# JlinkV9_RST.net
KiCad netlist of a schematic drawn in Altium Designer
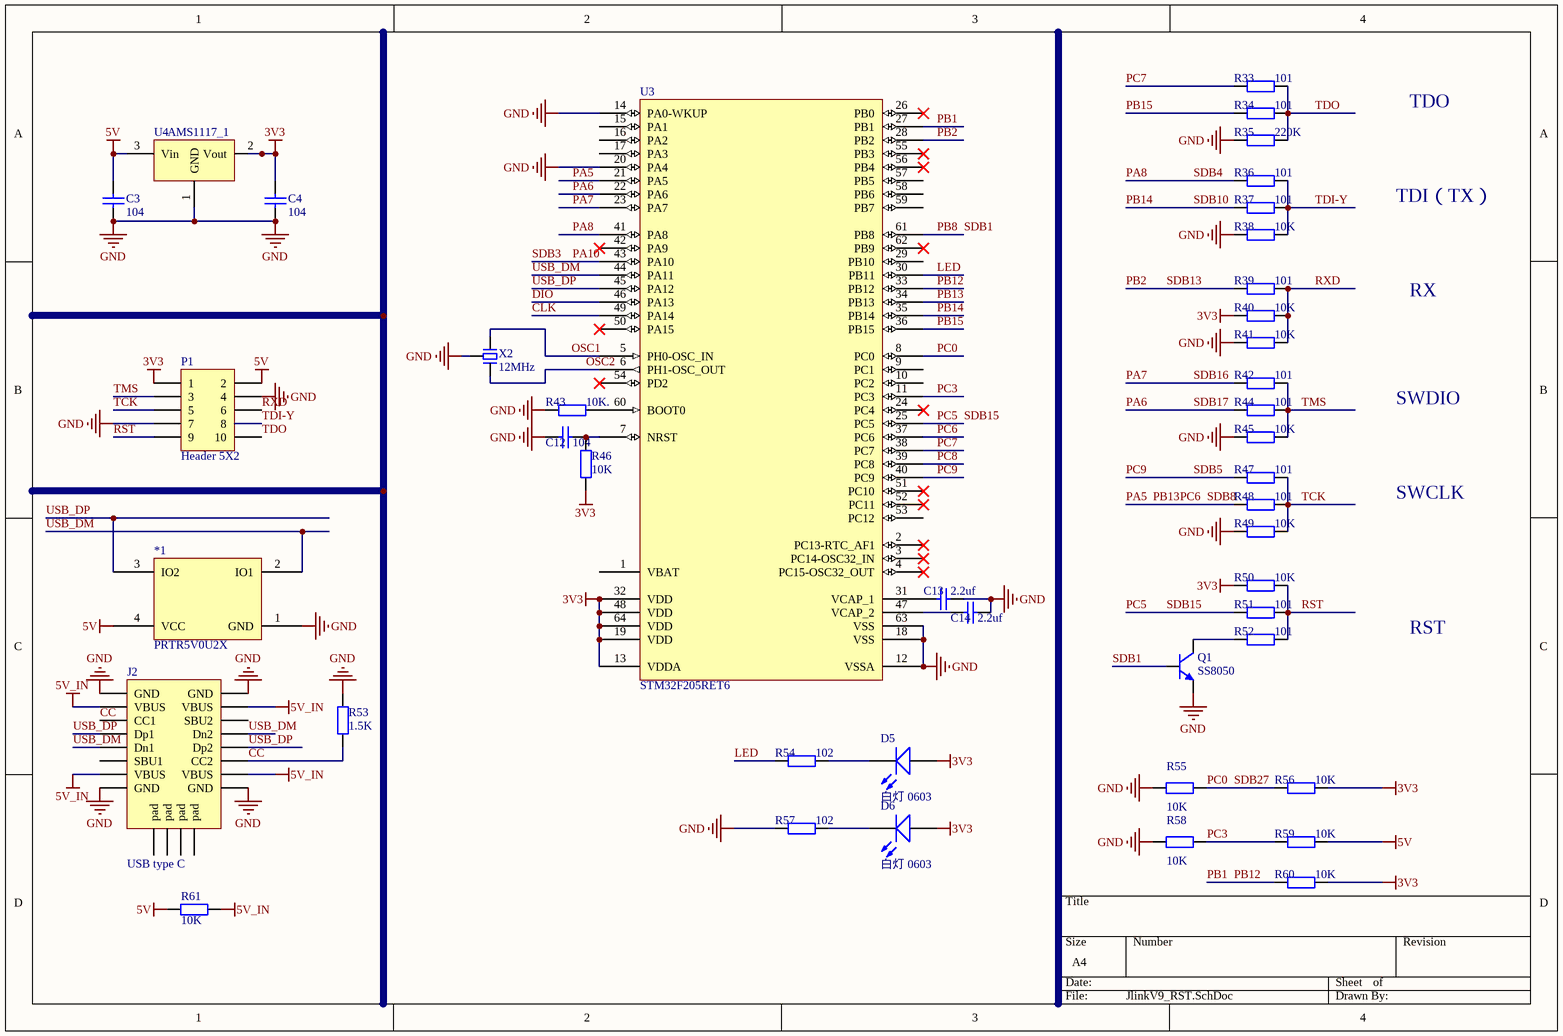
[diagram p0: JlinkV9_RST.SchDoc]

(export (version "E")
  (design (tool "Eeschema 10.0.6"))
  (components
    (comp (ref "*1")
      (value "PRTR5V0U2X")
      (footprint "LC-SOT-143")
      (libsource (lib "XKZ") (part "PRTR5V0U2X"))
    )
    (comp (ref "C3")
      (value "104")
      (footprint "LC-0603_C")
      (description "Polarized Capacitor (Radial)")
      (fields (field (name "PUBLISHER") "Altium Limited"))
      (libsource (lib "Fantasy") (part "Cap"))
    )
    (comp (ref "C4")
      (value "104")
      (footprint "LC-0603_C")
      (description "Polarized Capacitor (Radial)")
      (fields (field (name "PUBLISHER") "Altium Limited"))
      (libsource (lib "Fantasy") (part "Cap"))
    )
    (comp (ref "C12")
      (value "104")
      (footprint "LC-0603_C")
      (description "Polarized Capacitor (Radial)")
      (fields (field (name "PUBLISHER") "Altium Limited"))
      (libsource (lib "Fantasy") (part "Cap"))
    )
    (comp (ref "C13")
      (value "2.2uf")
      (footprint "LC-0603_C")
      (description "Polarized Capacitor (Radial)")
      (fields (field (name "Comment") "2.2UF") (field (name "PUBLISHER") "Altium Limited"))
      (libsource (lib "Fantasy") (part "Cap"))
    )
    (comp (ref "C14")
      (value "2.2uf")
      (footprint "LC-0603_C")
      (description "Polarized Capacitor (Radial)")
      (fields (field (name "Comment") "2.2UF") (field (name "PUBLISHER") "Altium Limited"))
      (libsource (lib "Fantasy") (part "Cap"))
    )
    (comp (ref "D5")
      (value "白灯 0603")
      (footprint "0603_LED_S1")
      (description "发光二极管")
      (libsource (lib "Miscellaneous Devices LC") (part "0603 白灯"))
    )
    (comp (ref "D6")
      (value "白灯 0603")
      (footprint "0603_LED_S1")
      (description "发光二极管")
      (libsource (lib "Miscellaneous Devices LC") (part "0603 白灯"))
    )
    (comp (ref "J2")
      (value "USB type C")
      (footprint "USB Type-C-16Pin_A")
      (libsource (lib "XKZ") (part "USB_C"))
    )
    (comp (ref "P1")
      (value "Header 5X2")
      (footprint "300S-2*5P 2.54MM_2")
      (description "Header, 5-Pin, Dual row")
      (fields (field (name "PUBLISHER") "Altium Limited"))
      (libsource (lib "Miscellaneous Connectors") (part "Header 5X2"))
    )
    (comp (ref "Q1")
      (value "SS8050")
      (footprint "SOT23-3N")
      (description "高频放大-NPN型")
      (fields (field (name "版权归属") "源创客"))
      (libsource (lib "3D库") (part "8050-SMD"))
    )
    (comp (ref "R33")
      (value "101")
      (footprint "LC-0603_R")
      (description "Resistor Chip")
      (fields (field (name "Comment") "100R") (field (name "PUBLISHER") "Altium Limited"))
      (libsource (lib "Fantasy") (part "Resistor"))
    )
    (comp (ref "R34")
      (value "101")
      (footprint "LC-0603_R")
      (description "Resistor Chip")
      (fields (field (name "Comment") "100R") (field (name "PUBLISHER") "Altium Limited"))
      (libsource (lib "Fantasy") (part "Resistor"))
    )
    (comp (ref "R35")
      (value "220K")
      (footprint "LC-0603_R")
      (description "Resistor Chip")
      (fields (field (name "Comment") "10K") (field (name "PUBLISHER") "Altium Limited"))
      (libsource (lib "Fantasy") (part "Resistor"))
    )
    (comp (ref "R36")
      (value "101")
      (footprint "LC-0603_R")
      (description "Resistor Chip")
      (fields (field (name "Comment") "100R") (field (name "PUBLISHER") "Altium Limited"))
      (libsource (lib "Fantasy") (part "Resistor"))
    )
    (comp (ref "R37")
      (value "101")
      (footprint "LC-0603_R")
      (description "Resistor Chip")
      (fields (field (name "Comment") "100R") (field (name "PUBLISHER") "Altium Limited"))
      (libsource (lib "Fantasy") (part "Resistor"))
    )
    (comp (ref "R38")
      (value "10K")
      (footprint "LC-0603_R")
      (description "Resistor Chip")
      (fields (field (name "PUBLISHER") "Altium Limited"))
      (libsource (lib "Fantasy") (part "Resistor"))
    )
    (comp (ref "R39")
      (value "101")
      (footprint "LC-0603_R")
      (description "Resistor Chip")
      (fields (field (name "Comment") "100R") (field (name "PUBLISHER") "Altium Limited"))
      (libsource (lib "Fantasy") (part "Resistor"))
    )
    (comp (ref "R40")
      (value "10K")
      (footprint "LC-0603_R")
      (description "Resistor Chip")
      (fields (field (name "PUBLISHER") "Altium Limited"))
      (libsource (lib "Fantasy") (part "Resistor"))
    )
    (comp (ref "R41")
      (value "10K")
      (footprint "LC-0603_R")
      (description "Resistor Chip")
      (fields (field (name "Comment") "NC") (field (name "PUBLISHER") "Altium Limited"))
      (libsource (lib "Fantasy") (part "Resistor"))
    )
    (comp (ref "R42")
      (value "101")
      (footprint "LC-0603_R")
      (description "Resistor Chip")
      (fields (field (name "Comment") "100R") (field (name "PUBLISHER") "Altium Limited"))
      (libsource (lib "Fantasy") (part "Resistor"))
    )
    (comp (ref "R43")
      (value "10K.")
      (footprint "LC-0603_R")
      (description "Resistor Chip")
      (fields (field (name "Comment") "10K") (field (name "PUBLISHER") "Altium Limited"))
      (libsource (lib "Fantasy") (part "Resistor"))
    )
    (comp (ref "R44")
      (value "101")
      (footprint "LC-0603_R")
      (description "Resistor Chip")
      (fields (field (name "Comment") "100R") (field (name "PUBLISHER") "Altium Limited"))
      (libsource (lib "Fantasy") (part "Resistor"))
    )
    (comp (ref "R45")
      (value "10K")
      (footprint "LC-0603_R")
      (description "Resistor Chip")
      (fields (field (name "PUBLISHER") "Altium Limited"))
      (libsource (lib "Fantasy") (part "Resistor"))
    )
    (comp (ref "R46")
      (value "10K")
      (footprint "LC-0603_R")
      (description "Resistor Chip")
      (fields (field (name "PUBLISHER") "Altium Limited"))
      (libsource (lib "") (part "Resistor_1"))
    )
    (comp (ref "R47")
      (value "101")
      (footprint "LC-0603_R")
      (description "Resistor Chip")
      (fields (field (name "Comment") "100R") (field (name "PUBLISHER") "Altium Limited"))
      (libsource (lib "Fantasy") (part "Resistor"))
    )
    (comp (ref "R48")
      (value "101")
      (footprint "LC-0603_R")
      (description "Resistor Chip")
      (fields (field (name "Comment") "100R") (field (name "PUBLISHER") "Altium Limited"))
      (libsource (lib "Fantasy") (part "Resistor"))
    )
    (comp (ref "R49")
      (value "10K")
      (footprint "LC-0603_R")
      (description "Resistor Chip")
      (fields (field (name "PUBLISHER") "Altium Limited"))
      (libsource (lib "Fantasy") (part "Resistor"))
    )
    (comp (ref "R50")
      (value "10K")
      (footprint "LC-0603_R")
      (description "Resistor Chip")
      (fields (field (name "Comment") "100R") (field (name "PUBLISHER") "Altium Limited"))
      (libsource (lib "Fantasy") (part "Resistor"))
    )
    (comp (ref "R51")
      (value "101")
      (footprint "LC-0603_R")
      (description "Resistor Chip")
      (fields (field (name "Comment") "100R") (field (name "PUBLISHER") "Altium Limited"))
      (libsource (lib "Fantasy") (part "Resistor"))
    )
    (comp (ref "R52")
      (value "101")
      (footprint "LC-0603_R")
      (description "Resistor Chip")
      (fields (field (name "Comment") "100R") (field (name "PUBLISHER") "Altium Limited"))
      (libsource (lib "Fantasy") (part "Resistor"))
    )
    (comp (ref "R53")
      (value "1.5K")
      (footprint "LC-0603_R")
      (description "Resistor")
      (fields (field (name "Comment") "1K") (field (name "PUBLISHER") "Altium Limited"))
      (libsource (lib "XKZ") (part "Res2"))
    )
    (comp (ref "R54")
      (value "102")
      (footprint "LC-0603_R")
      (description "Resistor Chip")
      (fields (field (name "Comment") "1K") (field (name "PUBLISHER") "Altium Limited"))
      (libsource (lib "Fantasy") (part "Resistor"))
    )
    (comp (ref "R55")
      (value "10K")
      (footprint "LC-0603_R")
      (description "Resistor Chip")
      (fields (field (name "PUBLISHER") "Altium Limited"))
      (libsource (lib "Fantasy") (part "Resistor"))
    )
    (comp (ref "R56")
      (value "10K")
      (footprint "LC-0603_R")
      (description "Resistor Chip")
      (fields (field (name "PUBLISHER") "Altium Limited"))
      (libsource (lib "Fantasy") (part "Resistor"))
    )
    (comp (ref "R57")
      (value "102")
      (footprint "LC-0603_R")
      (description "Resistor Chip")
      (fields (field (name "Comment") "1K") (field (name "PUBLISHER") "Altium Limited"))
      (libsource (lib "Fantasy") (part "Resistor"))
    )
    (comp (ref "R58")
      (value "10K")
      (footprint "LC-0603_R")
      (description "Resistor Chip")
      (fields (field (name "PUBLISHER") "Altium Limited"))
      (libsource (lib "Fantasy") (part "Resistor"))
    )
    (comp (ref "R59")
      (value "10K")
      (footprint "LC-0603_R")
      (description "Resistor Chip")
      (fields (field (name "PUBLISHER") "Altium Limited"))
      (libsource (lib "Fantasy") (part "Resistor"))
    )
    (comp (ref "R60")
      (value "10K")
      (footprint "LC-0603_R")
      (description "Resistor Chip")
      (fields (field (name "PUBLISHER") "Altium Limited"))
      (libsource (lib "Fantasy") (part "Resistor"))
    )
    (comp (ref "R61")
      (value "10K")
      (footprint "LC-0805_R")
      (description "Resistor")
      (fields (field (name "Comment") "1A保险丝") (field (name "PUBLISHER") "Altium Limited"))
      (libsource (lib "") (part "Res2_1"))
    )
    (comp (ref "U3")
      (value "STM32F205RET6")
      (footprint "LQFP64 10x10_N")
      (description "Microcontroller   ST")
      (libsource (lib "Fantasy") (part "STM32F205RET6"))
    )
    (comp (ref "U4")
      (value "AMS1117_1")
      (footprint "LC-SOT-223")
      (description "3.3V电压转换器AMS1117")
      (libsource (lib "自创") (part "AMS1117_1"))
    )
    (comp (ref "X2")
      (value "12MHz")
      (footprint "3脚晶振")
      (description "3脚无源晶振")
      (fields (field (name "版权归属") "源创客"))
      (libsource (lib "ATKF405 V1.1") (part "XTAL-3P"))
    )
  )
  (nets
    (net (code "1") (name "/CC") (class "Default")
      (node (ref "J2") (pin "A5") (pinfunction "CC1_A5") (pintype "passive"))
      (node (ref "J2") (pin "B5") (pinfunction "CC2_B5") (pintype "passive"))
      (node (ref "R53") (pin "2") (pinfunction "2_2") (pintype "passive"))
    )
    (net (code "2") (name "/CLK") (class "Default")
      (node (ref "U3") (pin "49") (pinfunction "PA14_49") (pintype "bidirectional"))
    )
    (net (code "3") (name "/DIO") (class "Default")
      (node (ref "U3") (pin "46") (pinfunction "PA13_46") (pintype "bidirectional"))
    )
    (net (code "4") (name "/LED") (class "Default")
      (node (ref "R54") (pin "1") (pinfunction "1_1") (pintype "passive"))
      (node (ref "U3") (pin "30") (pinfunction "PB11_30") (pintype "bidirectional"))
    )
    (net (code "5") (name "/OSC1") (class "Default")
      (node (ref "U3") (pin "5") (pinfunction "PH0-OSC_IN_5") (pintype "input"))
      (node (ref "X2") (pin "1") (pinfunction "1_1") (pintype "passive"))
    )
    (net (code "6") (name "/OSC2") (class "Default")
      (node (ref "U3") (pin "6") (pinfunction "PH1-OSC_OUT_6") (pintype "output"))
      (node (ref "X2") (pin "2") (pinfunction "2_2") (pintype "passive"))
    )
    (net (code "7") (name "/PA5") (class "Default")
      (node (ref "R48") (pin "1") (pinfunction "1_1") (pintype "passive"))
      (node (ref "U3") (pin "21") (pinfunction "PA5_21") (pintype "bidirectional"))
      (node (ref "U3") (pin "34") (pinfunction "PB13_34") (pintype "bidirectional"))
      (node (ref "U3") (pin "37") (pinfunction "PC6_37") (pintype "bidirectional"))
    )
    (net (code "8") (name "/PA6") (class "Default")
      (node (ref "R44") (pin "1") (pinfunction "1_1") (pintype "passive"))
      (node (ref "U3") (pin "22") (pinfunction "PA6_22") (pintype "bidirectional"))
    )
    (net (code "9") (name "/PA7") (class "Default")
      (node (ref "R42") (pin "1") (pinfunction "1_1") (pintype "passive"))
      (node (ref "U3") (pin "23") (pinfunction "PA7_23") (pintype "bidirectional"))
    )
    (net (code "10") (name "/PA8") (class "Default")
      (node (ref "R36") (pin "1") (pinfunction "1_1") (pintype "passive"))
      (node (ref "U3") (pin "41") (pinfunction "PA8_41") (pintype "bidirectional"))
    )
    (net (code "11") (name "/PA10") (class "Default")
      (node (ref "U3") (pin "43") (pinfunction "PA10_43") (pintype "bidirectional"))
    )
    (net (code "12") (name "/PB1") (class "Default")
      (node (ref "R60") (pin "1") (pinfunction "1_1") (pintype "passive"))
      (node (ref "U3") (pin "27") (pinfunction "PB1_27") (pintype "bidirectional"))
      (node (ref "U3") (pin "33") (pinfunction "PB12_33") (pintype "bidirectional"))
    )
    (net (code "13") (name "/PB2") (class "Default")
      (node (ref "R39") (pin "1") (pinfunction "1_1") (pintype "passive"))
      (node (ref "U3") (pin "28") (pinfunction "PB2_28") (pintype "bidirectional"))
    )
    (net (code "14") (name "/PB8") (class "Default")
      (node (ref "Q1") (pin "1") (pinfunction "B_1") (pintype "passive"))
      (node (ref "U3") (pin "61") (pinfunction "PB8_61") (pintype "bidirectional"))
    )
    (net (code "15") (name "/PB14") (class "Default")
      (node (ref "R37") (pin "1") (pinfunction "1_1") (pintype "passive"))
      (node (ref "U3") (pin "35") (pinfunction "PB14_35") (pintype "bidirectional"))
    )
    (net (code "16") (name "/PB15") (class "Default")
      (node (ref "R34") (pin "1") (pinfunction "1_1") (pintype "passive"))
      (node (ref "U3") (pin "36") (pinfunction "PB15_36") (pintype "bidirectional"))
    )
    (net (code "17") (name "/PC0") (class "Default")
      (node (ref "R55") (pin "2") (pinfunction "2_2") (pintype "passive"))
      (node (ref "R56") (pin "1") (pinfunction "1_1") (pintype "passive"))
      (node (ref "U3") (pin "8") (pinfunction "PC0_8") (pintype "bidirectional"))
    )
    (net (code "18") (name "/PC3") (class "Default")
      (node (ref "R58") (pin "2") (pinfunction "2_2") (pintype "passive"))
      (node (ref "R59") (pin "1") (pinfunction "1_1") (pintype "passive"))
      (node (ref "U3") (pin "11") (pinfunction "PC3_11") (pintype "bidirectional"))
    )
    (net (code "19") (name "/PC5") (class "Default")
      (node (ref "R51") (pin "1") (pinfunction "1_1") (pintype "passive"))
      (node (ref "U3") (pin "25") (pinfunction "PC5_25") (pintype "bidirectional"))
    )
    (net (code "20") (name "/PC7") (class "Default")
      (node (ref "R33") (pin "1") (pinfunction "1_1") (pintype "passive"))
      (node (ref "U3") (pin "38") (pinfunction "PC7_38") (pintype "bidirectional"))
    )
    (net (code "21") (name "/PC8") (class "Default")
      (node (ref "U3") (pin "39") (pinfunction "PC8_39") (pintype "bidirectional"))
    )
    (net (code "22") (name "/PC9") (class "Default")
      (node (ref "R47") (pin "1") (pinfunction "1_1") (pintype "passive"))
      (node (ref "U3") (pin "40") (pinfunction "PC9_40") (pintype "bidirectional"))
    )
    (net (code "23") (name "/RST") (class "Default")
      (node (ref "P1") (pin "9") (pinfunction "9_9") (pintype "passive"))
      (node (ref "R50") (pin "2") (pinfunction "2_2") (pintype "passive"))
      (node (ref "R51") (pin "2") (pinfunction "2_2") (pintype "passive"))
      (node (ref "R52") (pin "2") (pinfunction "2_2") (pintype "passive"))
    )
    (net (code "24") (name "/RXD") (class "Default")
      (node (ref "P1") (pin "6") (pinfunction "6_6") (pintype "passive"))
      (node (ref "R39") (pin "2") (pinfunction "2_2") (pintype "passive"))
      (node (ref "R40") (pin "2") (pinfunction "2_2") (pintype "passive"))
      (node (ref "R41") (pin "2") (pinfunction "2_2") (pintype "passive"))
    )
    (net (code "25") (name "/TCK") (class "Default")
      (node (ref "P1") (pin "5") (pinfunction "5_5") (pintype "passive"))
      (node (ref "R47") (pin "2") (pinfunction "2_2") (pintype "passive"))
      (node (ref "R48") (pin "2") (pinfunction "2_2") (pintype "passive"))
      (node (ref "R49") (pin "2") (pinfunction "2_2") (pintype "passive"))
    )
    (net (code "26") (name "/TDI-Y") (class "Default")
      (node (ref "P1") (pin "8") (pinfunction "8_8") (pintype "passive"))
      (node (ref "R36") (pin "2") (pinfunction "2_2") (pintype "passive"))
      (node (ref "R37") (pin "2") (pinfunction "2_2") (pintype "passive"))
      (node (ref "R38") (pin "2") (pinfunction "2_2") (pintype "passive"))
    )
    (net (code "27") (name "/TDO") (class "Default")
      (node (ref "P1") (pin "10") (pinfunction "10_10") (pintype "passive"))
      (node (ref "R33") (pin "2") (pinfunction "2_2") (pintype "passive"))
      (node (ref "R34") (pin "2") (pinfunction "2_2") (pintype "passive"))
      (node (ref "R35") (pin "2") (pinfunction "2_2") (pintype "passive"))
    )
    (net (code "28") (name "/TMS") (class "Default")
      (node (ref "P1") (pin "3") (pinfunction "3_3") (pintype "passive"))
      (node (ref "R42") (pin "2") (pinfunction "2_2") (pintype "passive"))
      (node (ref "R44") (pin "2") (pinfunction "2_2") (pintype "passive"))
      (node (ref "R45") (pin "2") (pinfunction "2_2") (pintype "passive"))
    )
    (net (code "29") (name "/USB_DM") (class "Default")
      (node (ref "*1") (pin "2") (pinfunction "IO1_2") (pintype "passive"))
      (node (ref "J2") (pin "A7") (pinfunction "Dn1_A7") (pintype "passive"))
      (node (ref "J2") (pin "B7") (pinfunction "Dn2_B7") (pintype "passive"))
      (node (ref "U3") (pin "44") (pinfunction "PA11_44") (pintype "bidirectional"))
    )
    (net (code "30") (name "/USB_DP") (class "Default")
      (node (ref "*1") (pin "3") (pinfunction "IO2_3") (pintype "passive"))
      (node (ref "J2") (pin "A6") (pinfunction "Dp1_A6") (pintype "passive"))
      (node (ref "J2") (pin "B6") (pinfunction "Dp2_B6") (pintype "passive"))
      (node (ref "U3") (pin "45") (pinfunction "PA12_45") (pintype "bidirectional"))
    )
    (net (code "31") (name "3V3") (class "Default")
      (node (ref "C4") (pin "2") (pinfunction "2_2") (pintype "passive"))
      (node (ref "D5") (pin "A") (pinfunction "A_A") (pintype "passive"))
      (node (ref "D6") (pin "A") (pinfunction "A_A") (pintype "passive"))
      (node (ref "P1") (pin "1") (pinfunction "1_1") (pintype "passive"))
      (node (ref "R40") (pin "1") (pinfunction "1_1") (pintype "passive"))
      (node (ref "R46") (pin "1") (pinfunction "1_1") (pintype "passive"))
      (node (ref "R50") (pin "1") (pinfunction "1_1") (pintype "passive"))
      (node (ref "R56") (pin "2") (pinfunction "2_2") (pintype "passive"))
      (node (ref "R60") (pin "2") (pinfunction "2_2") (pintype "passive"))
      (node (ref "U3") (pin "13") (pinfunction "VDDA_13") (pintype "power_in"))
      (node (ref "U3") (pin "19") (pinfunction "VDD_19") (pintype "power_in"))
      (node (ref "U3") (pin "32") (pinfunction "VDD_32") (pintype "power_in"))
      (node (ref "U3") (pin "48") (pinfunction "VDD_48") (pintype "power_in"))
      (node (ref "U3") (pin "64") (pinfunction "VDD_64") (pintype "power_in"))
      (node (ref "U4") (pin "2") (pinfunction "Vout_2") (pintype "passive"))
    )
    (net (code "32") (name "5V") (class "Default")
      (node (ref "*1") (pin "4") (pinfunction "VCC_4") (pintype "passive"))
      (node (ref "C3") (pin "2") (pinfunction "2_2") (pintype "passive"))
      (node (ref "P1") (pin "2") (pinfunction "2_2") (pintype "passive"))
      (node (ref "R59") (pin "2") (pinfunction "2_2") (pintype "passive"))
      (node (ref "R61") (pin "1") (pinfunction "1_1") (pintype "passive"))
      (node (ref "U4") (pin "3") (pinfunction "Vin_3") (pintype "passive"))
    )
    (net (code "33") (name "5V_IN") (class "Default")
      (node (ref "J2") (pin "A4") (pinfunction "VBUS_A4") (pintype "passive"))
      (node (ref "J2") (pin "A9") (pinfunction "VBUS_A9") (pintype "passive"))
      (node (ref "J2") (pin "B4") (pinfunction "VBUS_B4") (pintype "passive"))
      (node (ref "J2") (pin "B9") (pinfunction "VBUS_B9") (pintype "passive"))
      (node (ref "R61") (pin "2") (pinfunction "2_2") (pintype "passive"))
    )
    (net (code "34") (name "GND") (class "Default")
      (node (ref "*1") (pin "1") (pinfunction "GND_1") (pintype "passive"))
      (node (ref "C12") (pin "2") (pinfunction "2_2") (pintype "passive"))
      (node (ref "C13") (pin "1") (pinfunction "1_1") (pintype "passive"))
      (node (ref "C14") (pin "1") (pinfunction "1_1") (pintype "passive"))
      (node (ref "C3") (pin "1") (pinfunction "1_1") (pintype "passive"))
      (node (ref "C4") (pin "1") (pinfunction "1_1") (pintype "passive"))
      (node (ref "J2") (pin "A1") (pinfunction "GND_A1") (pintype "passive"))
      (node (ref "J2") (pin "A12") (pinfunction "GND_A12") (pintype "passive"))
      (node (ref "J2") (pin "B1") (pinfunction "GND_B1") (pintype "passive"))
      (node (ref "J2") (pin "B12") (pinfunction "GND_B12") (pintype "passive"))
      (node (ref "P1") (pin "4") (pinfunction "4_4") (pintype "passive"))
      (node (ref "P1") (pin "7") (pinfunction "7_7") (pintype "passive"))
      (node (ref "Q1") (pin "2") (pinfunction "E_2") (pintype "passive"))
      (node (ref "R35") (pin "1") (pinfunction "1_1") (pintype "passive"))
      (node (ref "R38") (pin "1") (pinfunction "1_1") (pintype "passive"))
      (node (ref "R41") (pin "1") (pinfunction "1_1") (pintype "passive"))
      (node (ref "R43") (pin "1") (pinfunction "1_1") (pintype "passive"))
      (node (ref "R45") (pin "1") (pinfunction "1_1") (pintype "passive"))
      (node (ref "R49") (pin "1") (pinfunction "1_1") (pintype "passive"))
      (node (ref "R53") (pin "1") (pinfunction "1_1") (pintype "passive"))
      (node (ref "R55") (pin "1") (pinfunction "1_1") (pintype "passive"))
      (node (ref "R57") (pin "1") (pinfunction "1_1") (pintype "passive"))
      (node (ref "R58") (pin "1") (pinfunction "1_1") (pintype "passive"))
      (node (ref "U3") (pin "12") (pinfunction "VSSA_12") (pintype "power_in"))
      (node (ref "U3") (pin "14") (pinfunction "PA0-WKUP_14") (pintype "bidirectional"))
      (node (ref "U3") (pin "18") (pinfunction "VSS_18") (pintype "power_in"))
      (node (ref "U3") (pin "20") (pinfunction "PA4_20") (pintype "bidirectional"))
      (node (ref "U3") (pin "63") (pinfunction "VSS_63") (pintype "power_in"))
      (node (ref "U4") (pin "1") (pinfunction "GND_1") (pintype "passive"))
      (node (ref "X2") (pin "3") (pinfunction "3_3") (pintype "passive"))
    )
    (net (code "35") (name "Net-(D5-PadK)") (class "Default")
      (node (ref "D5") (pin "K") (pinfunction "K_K") (pintype "passive"))
      (node (ref "R54") (pin "2") (pinfunction "2_2") (pintype "passive"))
    )
    (net (code "36") (name "Net-(D6-PadK)") (class "Default")
      (node (ref "D6") (pin "K") (pinfunction "K_K") (pintype "passive"))
      (node (ref "R57") (pin "2") (pinfunction "2_2") (pintype "passive"))
    )
    (net (code "37") (name "Net-(Q1-C)") (class "Default")
      (node (ref "Q1") (pin "3") (pinfunction "C_3") (pintype "passive"))
      (node (ref "R52") (pin "1") (pinfunction "1_1") (pintype "passive"))
    )
    (net (code "38") (name "Net-(U3-BOOT0)") (class "Default")
      (node (ref "R43") (pin "2") (pinfunction "2_2") (pintype "passive"))
      (node (ref "U3") (pin "60") (pinfunction "BOOT0_60") (pintype "input"))
    )
    (net (code "39") (name "Net-(U3-NRST)") (class "Default")
      (node (ref "C12") (pin "1") (pinfunction "1_1") (pintype "passive"))
      (node (ref "R46") (pin "2") (pinfunction "2_2") (pintype "passive"))
      (node (ref "U3") (pin "7") (pinfunction "NRST_7") (pintype "bidirectional"))
    )
    (net (code "40") (name "Net-(U3-VCAP_1)") (class "Default")
      (node (ref "C13") (pin "2") (pinfunction "2_2") (pintype "passive"))
      (node (ref "U3") (pin "31") (pinfunction "VCAP_1_31") (pintype "power_in"))
    )
    (net (code "41") (name "Net-(U3-VCAP_2)") (class "Default")
      (node (ref "C14") (pin "2") (pinfunction "2_2") (pintype "passive"))
      (node (ref "U3") (pin "47") (pinfunction "VCAP_2_47") (pintype "power_in"))
    )
    (net (code "42") (name "unconnected-(J2-SBU1-PadA8)") (class "Default")
      (node (ref "J2") (pin "A8") (pinfunction "SBU1_A8") (pintype "passive"))
    )
    (net (code "43") (name "unconnected-(J2-SBU2-PadB8)") (class "Default")
      (node (ref "J2") (pin "B8") (pinfunction "SBU2_B8") (pintype "passive"))
    )
    (net (code "44") (name "unconnected-(J2-pad-Pad0)") (class "Default")
      (node (ref "J2") (pin "0") (pinfunction "pad_0") (pintype "passive"))
    )
    (net (code "45") (name "unconnected-(J2-pad-Pad0)_1") (class "Default")
      (node (ref "J2") (pin "0") (pinfunction "pad_0") (pintype "passive"))
    )
    (net (code "46") (name "unconnected-(J2-pad-Pad0)_2") (class "Default")
      (node (ref "J2") (pin "0") (pinfunction "pad_0") (pintype "passive"))
    )
    (net (code "47") (name "unconnected-(J2-pad-Pad0)_3") (class "Default")
      (node (ref "J2") (pin "0") (pinfunction "pad_0") (pintype "passive"))
    )
    (net (code "48") (name "unconnected-(U3-PA1-Pad15)") (class "Default")
      (node (ref "U3") (pin "15") (pinfunction "PA1_15") (pintype "bidirectional"))
    )
    (net (code "49") (name "unconnected-(U3-PA2-Pad16)") (class "Default")
      (node (ref "U3") (pin "16") (pinfunction "PA2_16") (pintype "bidirectional"))
    )
    (net (code "50") (name "unconnected-(U3-PA3-Pad17)") (class "Default")
      (node (ref "U3") (pin "17") (pinfunction "PA3_17") (pintype "bidirectional"))
    )
    (net (code "51") (name "unconnected-(U3-PA9-Pad42)") (class "Default")
      (node (ref "U3") (pin "42") (pinfunction "PA9_42") (pintype "bidirectional+no_connect"))
    )
    (net (code "52") (name "unconnected-(U3-PA15-Pad50)") (class "Default")
      (node (ref "U3") (pin "50") (pinfunction "PA15_50") (pintype "bidirectional+no_connect"))
    )
    (net (code "53") (name "unconnected-(U3-PB0-Pad26)") (class "Default")
      (node (ref "U3") (pin "26") (pinfunction "PB0_26") (pintype "bidirectional+no_connect"))
    )
    (net (code "54") (name "unconnected-(U3-PB3-Pad55)") (class "Default")
      (node (ref "U3") (pin "55") (pinfunction "PB3_55") (pintype "bidirectional+no_connect"))
    )
    (net (code "55") (name "unconnected-(U3-PB4-Pad56)") (class "Default")
      (node (ref "U3") (pin "56") (pinfunction "PB4_56") (pintype "bidirectional+no_connect"))
    )
    (net (code "56") (name "unconnected-(U3-PB5-Pad57)") (class "Default")
      (node (ref "U3") (pin "57") (pinfunction "PB5_57") (pintype "bidirectional"))
    )
    (net (code "57") (name "unconnected-(U3-PB6-Pad58)") (class "Default")
      (node (ref "U3") (pin "58") (pinfunction "PB6_58") (pintype "bidirectional"))
    )
    (net (code "58") (name "unconnected-(U3-PB7-Pad59)") (class "Default")
      (node (ref "U3") (pin "59") (pinfunction "PB7_59") (pintype "bidirectional"))
    )
    (net (code "59") (name "unconnected-(U3-PB9-Pad62)") (class "Default")
      (node (ref "U3") (pin "62") (pinfunction "PB9_62") (pintype "bidirectional+no_connect"))
    )
    (net (code "60") (name "unconnected-(U3-PB10-Pad29)") (class "Default")
      (node (ref "U3") (pin "29") (pinfunction "PB10_29") (pintype "bidirectional"))
    )
    (net (code "61") (name "unconnected-(U3-PC1-Pad9)") (class "Default")
      (node (ref "U3") (pin "9") (pinfunction "PC1_9") (pintype "bidirectional"))
    )
    (net (code "62") (name "unconnected-(U3-PC2-Pad10)") (class "Default")
      (node (ref "U3") (pin "10") (pinfunction "PC2_10") (pintype "bidirectional"))
    )
    (net (code "63") (name "unconnected-(U3-PC4-Pad24)") (class "Default")
      (node (ref "U3") (pin "24") (pinfunction "PC4_24") (pintype "bidirectional+no_connect"))
    )
    (net (code "64") (name "unconnected-(U3-PC10-Pad51)") (class "Default")
      (node (ref "U3") (pin "51") (pinfunction "PC10_51") (pintype "bidirectional+no_connect"))
    )
    (net (code "65") (name "unconnected-(U3-PC11-Pad52)") (class "Default")
      (node (ref "U3") (pin "52") (pinfunction "PC11_52") (pintype "bidirectional+no_connect"))
    )
    (net (code "66") (name "unconnected-(U3-PC12-Pad53)") (class "Default")
      (node (ref "U3") (pin "53") (pinfunction "PC12_53") (pintype "bidirectional"))
    )
    (net (code "67") (name "unconnected-(U3-PC13-RTC_AF1-Pad2)") (class "Default")
      (node (ref "U3") (pin "2") (pinfunction "PC13-RTC_AF1_2") (pintype "bidirectional+no_connect"))
    )
    (net (code "68") (name "unconnected-(U3-PC14-OSC32_IN-Pad3)") (class "Default")
      (node (ref "U3") (pin "3") (pinfunction "PC14-OSC32_IN_3") (pintype "bidirectional+no_connect"))
    )
    (net (code "69") (name "unconnected-(U3-PC15-OSC32_OUT-Pad4)") (class "Default")
      (node (ref "U3") (pin "4") (pinfunction "PC15-OSC32_OUT_4") (pintype "bidirectional+no_connect"))
    )
    (net (code "70") (name "unconnected-(U3-PD2-Pad54)") (class "Default")
      (node (ref "U3") (pin "54") (pinfunction "PD2_54") (pintype "bidirectional+no_connect"))
    )
    (net (code "71") (name "unconnected-(U3-VBAT-Pad1)") (class "Default")
      (node (ref "U3") (pin "1") (pinfunction "VBAT_1") (pintype "power_in"))
    )
  )
)
